# Bodem_Sch.net
KiCad netlist of a schematic drawn in Altium Designer
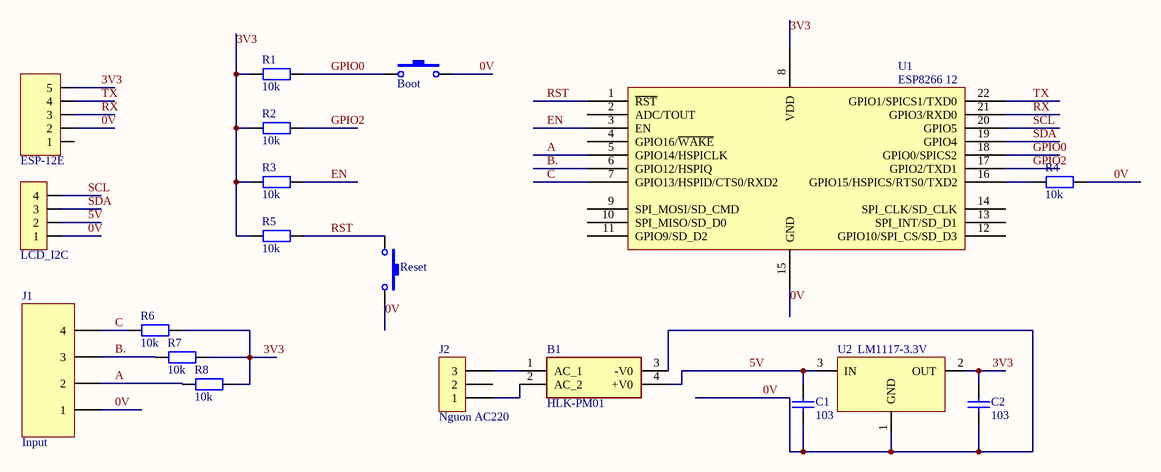
[diagram p0: Bodem_Sch.SchDoc]

(export (version "E")
  (design (tool "Eeschema 10.0.6"))
  (components
    (comp (ref "B1")
      (value "HLK-PM01")
      (footprint "HLKPM01:HLKPM01")
      (description "Ultra-compact power module")
      (libsource (lib "HLK-PM01") (part "HLK-PM01"))
    )
    (comp (ref "Boot")
      (value "Nut Nhan 2 Chan SMD 3x6x2.5")
      (footprint "Nut Nhan 2 Chan SMD 3x6x2.5")
      (libsource (lib "Component") (part "Nut Nhan 2 Chan SMD 3x6x2.5"))
    )
    (comp (ref "C1")
      (value "103")
      (footprint "tu 0603")
      (description "Dán")
      (libsource (lib "Tu dien") (part "Tu 0603 103 50V 10%"))
    )
    (comp (ref "C2")
      (value "103")
      (footprint "tu 0603")
      (description "Dán")
      (libsource (lib "Tu dien") (part "Tu 0603 103 50V 10%"))
    )
    (comp (ref "J1")
      (value "Input")
      (footprint "KF4-7.62")
      (fields
        (field (name "MANUFACTURER") "Würth Elektronik eiSos GmbH")
        (field (name "PARTNO") "691133710004")
        (field (name "CREATED BY") "Baojun Chen")
      )
      (libsource (lib "TechMT.VN_Lib_Project v2") (part "KF4"))
    )
    (comp (ref "J2")
      (value "Nguon AC220")
      (footprint "KF3-7.62")
      (fields
        (field (name "MANUFACTURER") "Würth Elektronik eiSos GmbH")
        (field (name "PARTNO") "691103110003")
        (field (name "CREATED BY") "Karrer Zheng")
      )
      (libsource (lib "TechMT.VN_Lib_Project v2") (part "KF3"))
    )
    (comp (ref "JP1")
      (value "ESP-12E")
      (footprint "JP 1x5 CT")
      (description "Cắm")
      (libsource (lib "Jump") (part "JP 1x5 2.54 Cai Thang"))
    )
    (comp (ref "JP2")
      (value "LCD_I2C")
      (footprint "JP 1x4 DT")
      (description "Cắm")
      (libsource (lib "Jump") (part "JP 1x4 2.54 Duc Thang"))
    )
    (comp (ref "R1")
      (value "10k")
      (footprint "tro smd 0603")
      (description "Dán")
      (libsource (lib "Dien Tro") (part "Tro 0603 5% 10k"))
    )
    (comp (ref "R2")
      (value "10k")
      (footprint "tro smd 0603")
      (description "Dán")
      (libsource (lib "Dien Tro") (part "Tro 0603 5% 10k"))
    )
    (comp (ref "R3")
      (value "10k")
      (footprint "tro smd 0603")
      (description "Dán")
      (libsource (lib "Dien Tro") (part "Tro 0603 5% 10k"))
    )
    (comp (ref "R4")
      (value "10k")
      (footprint "tro smd 0603")
      (description "Dán")
      (libsource (lib "Dien Tro") (part "Tro 0603 5% 10k"))
    )
    (comp (ref "R5")
      (value "10k")
      (footprint "tro smd 0603")
      (description "Dán")
      (libsource (lib "Dien Tro") (part "Tro 0603 5% 10k"))
    )
    (comp (ref "R6")
      (value "10k")
      (footprint "tro smd 0603")
      (description "Dán")
      (libsource (lib "Dien Tro") (part "Tro 0603 5% 10k"))
    )
    (comp (ref "R7")
      (value "10k")
      (footprint "tro smd 0603")
      (description "Dán")
      (libsource (lib "Dien Tro") (part "Tro 0603 5% 10k"))
    )
    (comp (ref "R8")
      (value "10k")
      (footprint "tro smd 0603")
      (description "Dán")
      (libsource (lib "Dien Tro") (part "Tro 0603 5% 10k"))
    )
    (comp (ref "Reset")
      (value "Nut Nhan 2 Chan SMD 3x6x2.5")
      (footprint "Nut Nhan 2 Chan SMD 3x6x2.5")
      (libsource (lib "Component") (part "Nut Nhan 2 Chan SMD 3x6x2.5"))
    )
    (comp (ref "U1")
      (value "ESP8266 12")
      (footprint "ESP8266 12")
      (description "ESP8266 12 22 Pin")
      (libsource (lib "IC") (part "ESP8266 12"))
    )
    (comp (ref "U2")
      (value "LM1117-3.3V")
      (footprint "SOT223")
      (description "800mA Low-Dropout Linear Regulator")
      (fields (field (name "CREATOR") "Nguyen Ba Bien"))
      (libsource (lib "TechMT.VN_Lib_Project v2") (part "LM1117"))
    )
  )
  (nets
    (net (code "1") (name "/0V") (class "Default")
      (node (ref "B1") (pin "3") (pinfunction "-V0_3") (pintype "passive"))
      (node (ref "Boot") (pin "2") (pinfunction "2_2") (pintype "passive"))
      (node (ref "C1") (pin "2") (pinfunction "2_2") (pintype "passive"))
      (node (ref "C2") (pin "2") (pinfunction "2_2") (pintype "passive"))
      (node (ref "J1") (pin "1") (pinfunction "1_1") (pintype "passive"))
      (node (ref "JP1") (pin "2") (pinfunction "2_2") (pintype "passive"))
      (node (ref "JP2") (pin "1") (pinfunction "1_1") (pintype "passive"))
      (node (ref "R4") (pin "2") (pinfunction "2_2") (pintype "passive"))
      (node (ref "Reset") (pin "2") (pinfunction "2_2") (pintype "passive"))
      (node (ref "U1") (pin "15") (pinfunction "GND_15") (pintype "passive"))
      (node (ref "U2") (pin "1") (pinfunction "GND_1") (pintype "passive"))
    )
    (net (code "2") (name "/3V3") (class "Default")
      (node (ref "C2") (pin "1") (pinfunction "1_1") (pintype "passive"))
      (node (ref "JP1") (pin "5") (pinfunction "5_5") (pintype "passive"))
      (node (ref "R1") (pin "1") (pinfunction "1_1") (pintype "passive"))
      (node (ref "R2") (pin "1") (pinfunction "1_1") (pintype "passive"))
      (node (ref "R3") (pin "1") (pinfunction "1_1") (pintype "passive"))
      (node (ref "R5") (pin "1") (pinfunction "1_1") (pintype "passive"))
      (node (ref "R6") (pin "2") (pinfunction "2_2") (pintype "passive"))
      (node (ref "R7") (pin "2") (pinfunction "2_2") (pintype "passive"))
      (node (ref "R8") (pin "2") (pinfunction "2_2") (pintype "passive"))
      (node (ref "U1") (pin "8") (pinfunction "VDD_8") (pintype "passive"))
      (node (ref "U2") (pin "2") (pinfunction "OUT_2") (pintype "passive"))
    )
    (net (code "3") (name "/5V") (class "Default")
      (node (ref "B1") (pin "4") (pinfunction "+V0_4") (pintype "passive"))
      (node (ref "C1") (pin "1") (pinfunction "1_1") (pintype "passive"))
      (node (ref "JP2") (pin "2") (pinfunction "2_2") (pintype "passive"))
      (node (ref "U2") (pin "3") (pinfunction "IN_3") (pintype "passive"))
    )
    (net (code "4") (name "/A") (class "Default")
      (node (ref "J1") (pin "2") (pinfunction "2_2") (pintype "passive"))
      (node (ref "R8") (pin "1") (pinfunction "1_1") (pintype "passive"))
      (node (ref "U1") (pin "5") (pinfunction "GPIO14/HSPICLK_5") (pintype "passive"))
    )
    (net (code "5") (name "/B.") (class "Default")
      (node (ref "J1") (pin "3") (pinfunction "3_3") (pintype "passive"))
      (node (ref "R7") (pin "1") (pinfunction "1_1") (pintype "passive"))
      (node (ref "U1") (pin "6") (pinfunction "GPIO12/HSPIQ_6") (pintype "passive"))
    )
    (net (code "6") (name "/C") (class "Default")
      (node (ref "J1") (pin "4") (pinfunction "4_4") (pintype "passive"))
      (node (ref "R6") (pin "1") (pinfunction "1_1") (pintype "passive"))
      (node (ref "U1") (pin "7") (pinfunction "GPIO13/HSPID/CTS0/RXD2_7") (pintype "passive"))
    )
    (net (code "7") (name "/EN") (class "Default")
      (node (ref "R3") (pin "2") (pinfunction "2_2") (pintype "passive"))
      (node (ref "U1") (pin "3") (pinfunction "EN_3") (pintype "passive"))
    )
    (net (code "8") (name "/GPIO0") (class "Default")
      (node (ref "Boot") (pin "1") (pinfunction "1_1") (pintype "passive"))
      (node (ref "R1") (pin "2") (pinfunction "2_2") (pintype "passive"))
      (node (ref "U1") (pin "18") (pinfunction "GPIO0/SPICS2_18") (pintype "passive"))
    )
    (net (code "9") (name "/GPIO2") (class "Default")
      (node (ref "R2") (pin "2") (pinfunction "2_2") (pintype "passive"))
      (node (ref "U1") (pin "17") (pinfunction "GPIO2/TXD1_17") (pintype "passive"))
    )
    (net (code "10") (name "/RST") (class "Default")
      (node (ref "R5") (pin "2") (pinfunction "2_2") (pintype "passive"))
      (node (ref "Reset") (pin "1") (pinfunction "1_1") (pintype "passive"))
      (node (ref "U1") (pin "1") (pinfunction "~{RST}_1") (pintype "passive"))
    )
    (net (code "11") (name "/RX") (class "Default")
      (node (ref "JP1") (pin "3") (pinfunction "3_3") (pintype "passive"))
      (node (ref "U1") (pin "21") (pinfunction "GPIO3/RXD0_21") (pintype "passive"))
    )
    (net (code "12") (name "/SCL") (class "Default")
      (node (ref "JP2") (pin "4") (pinfunction "4_4") (pintype "passive"))
      (node (ref "U1") (pin "20") (pinfunction "GPIO5_20") (pintype "passive"))
    )
    (net (code "13") (name "/SDA") (class "Default")
      (node (ref "JP2") (pin "3") (pinfunction "3_3") (pintype "passive"))
      (node (ref "U1") (pin "19") (pinfunction "GPIO4_19") (pintype "passive"))
    )
    (net (code "14") (name "/TX") (class "Default")
      (node (ref "JP1") (pin "4") (pinfunction "4_4") (pintype "passive"))
      (node (ref "U1") (pin "22") (pinfunction "GPIO1/SPICS1/TXD0_22") (pintype "passive"))
    )
    (net (code "15") (name "Net-(B1-AC_1)") (class "Default")
      (node (ref "B1") (pin "1") (pinfunction "AC_1_1") (pintype "passive"))
      (node (ref "J2") (pin "3") (pinfunction "3_3") (pintype "passive"))
    )
    (net (code "16") (name "Net-(B1-AC_2)") (class "Default")
      (node (ref "B1") (pin "2") (pinfunction "AC_2_2") (pintype "passive"))
      (node (ref "J2") (pin "1") (pinfunction "1_1") (pintype "passive"))
    )
    (net (code "17") (name "Net-(U1-GPIO15{slash}HSPICS{slash}RTS0{slash}TXD2)") (class "Default")
      (node (ref "R4") (pin "1") (pinfunction "1_1") (pintype "passive"))
      (node (ref "U1") (pin "16") (pinfunction "GPIO15/HSPICS/RTS0/TXD2_16") (pintype "passive"))
    )
    (net (code "18") (name "unconnected-(J2-Pad2)") (class "Default")
      (node (ref "J2") (pin "2") (pinfunction "2_2") (pintype "passive"))
    )
    (net (code "19") (name "unconnected-(JP1-Pad1)") (class "Default")
      (node (ref "JP1") (pin "1") (pinfunction "1_1") (pintype "passive"))
    )
    (net (code "20") (name "unconnected-(U1-ADC{slash}TOUT-Pad2)") (class "Default")
      (node (ref "U1") (pin "2") (pinfunction "ADC/TOUT_2") (pintype "passive"))
    )
    (net (code "21") (name "unconnected-(U1-GPIO9{slash}SD_D2-Pad11)") (class "Default")
      (node (ref "U1") (pin "11") (pinfunction "GPIO9/SD_D2_11") (pintype "passive"))
    )
    (net (code "22") (name "unconnected-(U1-GPIO10{slash}SPI_CS{slash}SD_D3-Pad12)") (class "Default")
      (node (ref "U1") (pin "12") (pinfunction "GPIO10/SPI_CS/SD_D3_12") (pintype "passive"))
    )
    (net (code "23") (name "unconnected-(U1-GPIO16{slash}~{WAKE}-Pad4)") (class "Default")
      (node (ref "U1") (pin "4") (pinfunction "GPIO16/~{WAKE}_4") (pintype "passive"))
    )
    (net (code "24") (name "unconnected-(U1-SPI_CLK{slash}SD_CLK-Pad14)") (class "Default")
      (node (ref "U1") (pin "14") (pinfunction "SPI_CLK/SD_CLK_14") (pintype "passive"))
    )
    (net (code "25") (name "unconnected-(U1-SPI_INT{slash}SD_D1-Pad13)") (class "Default")
      (node (ref "U1") (pin "13") (pinfunction "SPI_INT/SD_D1_13") (pintype "passive"))
    )
    (net (code "26") (name "unconnected-(U1-SPI_MISO{slash}SD_D0-Pad10)") (class "Default")
      (node (ref "U1") (pin "10") (pinfunction "SPI_MISO/SD_D0_10") (pintype "passive"))
    )
    (net (code "27") (name "unconnected-(U1-SPI_MOSI{slash}SD_CMD-Pad9)") (class "Default")
      (node (ref "U1") (pin "9") (pinfunction "SPI_MOSI/SD_CMD_9") (pintype "passive"))
    )
  )
)
